# Socket.net
KiCad netlist of a schematic drawn in Altium Designer
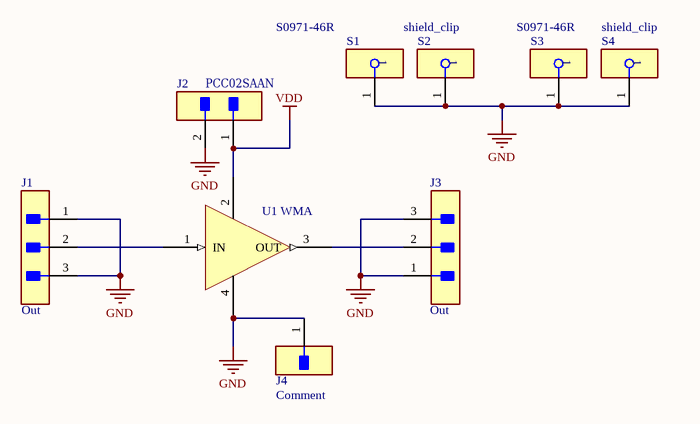
[diagram p0: Socket.SchDoc]

(export (version "E")
  (design (tool "Eeschema 10.0.6"))
  (components
    (comp (ref "J1")
      (value "Out")
      (footprint "FP-87224-3-MFG")
      (description "CONN HEADER VERT 3POS 2.54MM PCC03SAAN")
      (libsource (lib "") (part "CMP-2000-05697-2_1"))
    )
    (comp (ref "J2")
      (value "‎PCC02SAAN‎")
      (footprint "FP-TSW-102-07-G-S-MFG")
      (description "CONN HEADER VERT 2POS 2.54MM")
      (fields
        (field (name "MANUFACTURER") "Samtec")
        (field (name "MANUFACTURER PART NUMBER") "TSW-102-07-G-S")
      )
      (libsource (lib "Header1x3") (part "CMP-02766-000084-1"))
    )
    (comp (ref "J3")
      (value "Out")
      (footprint "FP-87224-3-MFG")
      (description "CONN HEADER VERT 3POS 2.54MM  PCC03SAAN")
      (libsource (lib "Header1x3") (part "CMP-2000-05697-2"))
    )
    (comp (ref "J4")
      (value "Comment")
      (footprint "FP-TSW-101-07-F-S-MFG")
      (description "CONN HEADER VERT 1POS PBC01SFAN")
      (libsource (lib "Header1x3") (part "CMP-02766-001403-1"))
    )
    (comp (ref "S1")
      (value "S0971-46R")
      (footprint "FP-S0971-46R-MFG")
      (description "RFI SHIELD CLIP MINI TIN SMD")
      (fields
        (field (name "MANUFACTURER") "Harwin")
        (field (name "OCTOPART") "https://octopart.com/s0971-46r-harwin-30988305")
      )
      (libsource (lib "Header1x3") (part "CMP-15817-000004-1"))
    )
    (comp (ref "S2")
      (value "shield_clip")
      (footprint "FP-S0971-46R-MFG")
      (description "RFI SHIELD CLIP MINI TIN SMD")
      (fields (field (name "MANUFACTURER") "Harwin") (field (name "MANUFACTURER PART NUMBER") "S0971-46R"))
      (libsource (lib "Header1x3") (part "CMP-15817-000004-1"))
    )
    (comp (ref "S3")
      (value "S0971-46R")
      (footprint "FP-S0971-46R-MFG")
      (description "RFI SHIELD CLIP MINI TIN SMD")
      (fields
        (field (name "MANUFACTURER") "Harwin")
        (field (name "OCTOPART") "https://octopart.com/s0971-46r-harwin-30988305")
      )
      (libsource (lib "Header1x3") (part "CMP-15817-000004-1"))
    )
    (comp (ref "S4")
      (value "shield_clip")
      (footprint "FP-S0971-46R-MFG")
      (description "RFI SHIELD CLIP MINI TIN SMD")
      (fields (field (name "MANUFACTURER") "Harwin") (field (name "MANUFACTURER PART NUMBER") "S0971-46R"))
      (libsource (lib "Header1x3") (part "CMP-15817-000004-1"))
    )
    (comp (ref "U1")
      (value "WMA")
      (footprint "WMA-Footprint-1")
      (description "WanTcom SMT Series Preamplifiers  0.6\"x0.4\" footprint")
      (libsource (lib "MRBEL") (part "WMA-Symbol-1"))
    )
  )
  (nets
    (net (code "1") (name "GND") (class "Default")
      (node (ref "J1") (pin "1") (pinfunction "1_1") (pintype "passive"))
      (node (ref "J1") (pin "3") (pinfunction "3_3") (pintype "passive"))
      (node (ref "J2") (pin "2") (pinfunction "2_2") (pintype "passive"))
      (node (ref "J3") (pin "1") (pinfunction "1_1") (pintype "passive"))
      (node (ref "J3") (pin "3") (pinfunction "3_3") (pintype "passive"))
      (node (ref "J4") (pin "1") (pinfunction "1_1") (pintype "passive"))
      (node (ref "S1") (pin "1") (pinfunction "1_1") (pintype "passive"))
      (node (ref "S2") (pin "1") (pinfunction "1_1") (pintype "passive"))
      (node (ref "S3") (pin "1") (pinfunction "1_1") (pintype "passive"))
      (node (ref "S4") (pin "1") (pinfunction "1_1") (pintype "passive"))
      (node (ref "U1") (pin "4") (pinfunction "4_4") (pintype "passive"))
    )
    (net (code "2") (name "Net-(U1-IN)") (class "Default")
      (node (ref "J1") (pin "2") (pinfunction "2_2") (pintype "passive"))
      (node (ref "U1") (pin "1") (pinfunction "IN_1") (pintype "input"))
    )
    (net (code "3") (name "Net-(U1-OUT)") (class "Default")
      (node (ref "J3") (pin "2") (pinfunction "2_2") (pintype "passive"))
      (node (ref "U1") (pin "3") (pinfunction "OUT_3") (pintype "output"))
    )
    (net (code "4") (name "VDD") (class "Default")
      (node (ref "J2") (pin "1") (pinfunction "1_1") (pintype "passive"))
      (node (ref "U1") (pin "2") (pinfunction "Vdd_2") (pintype "power_in"))
    )
  )
)
